# Square8.net
KiCad netlist of a schematic drawn in EAGLE
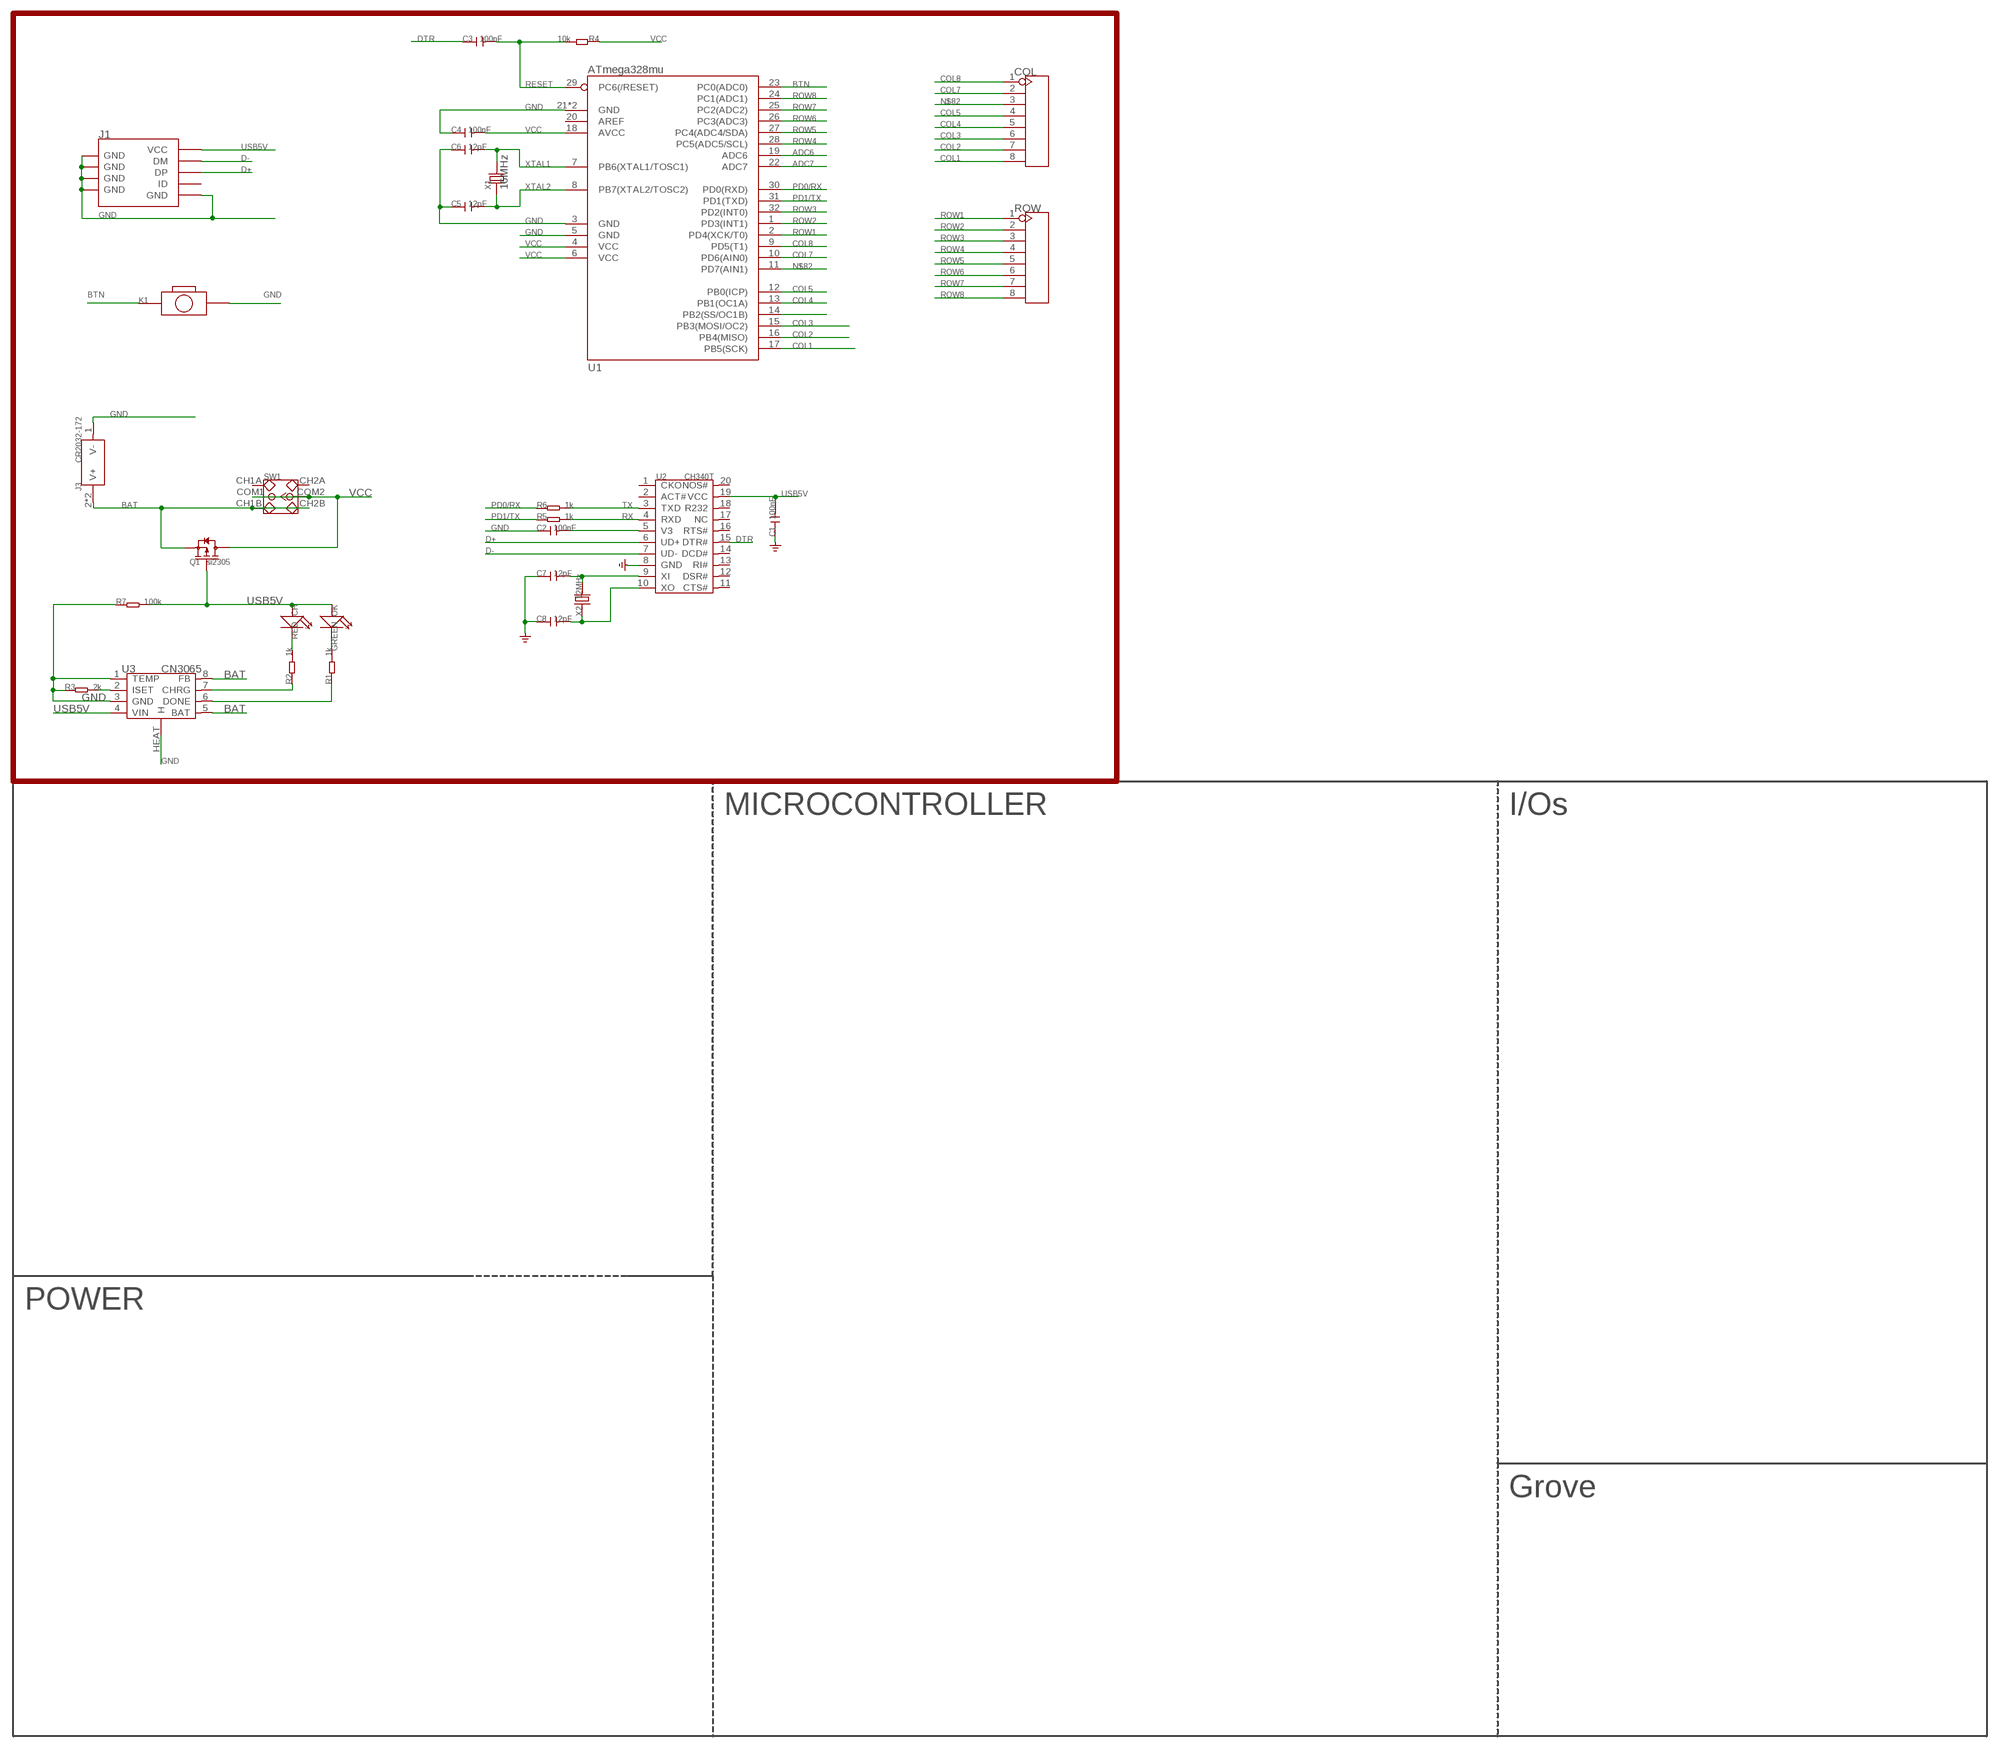
[diagram p0: schematic, sheet 1]

(export (version "E")
  (design (tool "Eeschema 10.0.6"))
  (components
    (comp (ref "C1")
      (value "100nF")
      (footprint "eagle-import:CERAMIC-2.54")
      (libsource (lib "eagle-import") (part "C'2.54'"))
    )
    (comp (ref "C2")
      (value "100nF")
      (footprint "eagle-import:CERAMIC-2.54")
      (libsource (lib "eagle-import") (part "C'2.54'"))
    )
    (comp (ref "C3")
      (value "100nF")
      (footprint "eagle-import:CERAMIC-2.54")
      (libsource (lib "eagle-import") (part "C'2.54'"))
    )
    (comp (ref "C4")
      (value "100nF")
      (footprint "eagle-import:CERAMIC-2.54")
      (libsource (lib "eagle-import") (part "C'2.54'"))
    )
    (comp (ref "C5")
      (value "12pF")
      (footprint "eagle-import:C0603")
      (libsource (lib "eagle-import") (part "C-0603"))
    )
    (comp (ref "C6")
      (value "12pF")
      (footprint "eagle-import:C0603")
      (libsource (lib "eagle-import") (part "C-0603"))
    )
    (comp (ref "C7")
      (value "12pF")
      (footprint "eagle-import:C0603")
      (libsource (lib "eagle-import") (part "C-0603"))
    )
    (comp (ref "C8")
      (value "12pF")
      (footprint "eagle-import:C0603")
      (libsource (lib "eagle-import") (part "C-0603"))
    )
    (comp (ref "CH")
      (value "RED")
      (footprint "eagle-import:LED-2P-2.54-3MM")
      (libsource (lib "eagle-import") (part "LED-3MM"))
    )
    (comp (ref "COL")
      (value "HEADER-8P-2.54")
      (footprint "eagle-import:8P-2.54")
      (libsource (lib "eagle-import") (part "HEADER-8P-2.54"))
    )
    (comp (ref "J1")
      (value "USB-MINIUSB-5P-MICRO")
      (footprint "eagle-import:MICRO-USB")
      (libsource (lib "eagle-import") (part "USB-MINIUSB-5P-MICRO"))
    )
    (comp (ref "J3")
      (value "CR2032-172")
      (footprint "eagle-import:2032-D20-CIRCLE")
      (libsource (lib "eagle-import") (part "HOLDER-BAT-CIRCLE"))
    )
    (comp (ref "K1")
      (value "BUTTON-2P'TS-1101F'")
      (footprint "eagle-import:2P-3.4X6.0X3.55H-90D")
      (libsource (lib "eagle-import") (part "BUTTON-2P'TS-1101F'"))
    )
    (comp (ref "OK")
      (value "GREEN")
      (footprint "eagle-import:LED-2P-2.54-3MM")
      (libsource (lib "eagle-import") (part "LED-3MM"))
    )
    (comp (ref "Q1")
      (value "si2305")
      (footprint "eagle-import:SOT23")
      (libsource (lib "eagle-import") (part "MOSFET-P'SI2323CDS/SI2305DS{lt}BR{gt}'"))
    )
    (comp (ref "R1")
      (value "1k")
      (footprint "eagle-import:R0204_7")
      (libsource (lib "eagle-import") (part "R-0204/7"))
    )
    (comp (ref "R2")
      (value "1k")
      (footprint "eagle-import:R0204_7")
      (libsource (lib "eagle-import") (part "R-0204/7"))
    )
    (comp (ref "R3")
      (value "2k")
      (footprint "eagle-import:R0204_7")
      (libsource (lib "eagle-import") (part "R-0204/7"))
    )
    (comp (ref "R4")
      (value "10k")
      (footprint "eagle-import:R0204_7")
      (libsource (lib "eagle-import") (part "R-0204/7"))
    )
    (comp (ref "R5")
      (value "1k")
      (footprint "eagle-import:R0204_7")
      (libsource (lib "eagle-import") (part "R-0204/7"))
    )
    (comp (ref "R6")
      (value "1k")
      (footprint "eagle-import:R0204_7")
      (libsource (lib "eagle-import") (part "R-0204/7"))
    )
    (comp (ref "R7")
      (value "100k")
      (footprint "eagle-import:R0603")
      (libsource (lib "eagle-import") (part "R-0603"))
    )
    (comp (ref "ROW")
      (value "HEADER-8P-2.54")
      (footprint "eagle-import:8P-2.54")
      (libsource (lib "eagle-import") (part "HEADER-8P-2.54"))
    )
    (comp (ref "SW1")
      (value "SWITCH-2CH-6P'90D'")
      (footprint "eagle-import:6P-2CH-2.5-9.1X3.5X3.2H-90D")
      (libsource (lib "eagle-import") (part "SWITCH-2CH-6P'90D'"))
    )
    (comp (ref "U1")
      (value "ATmega328mu")
      (footprint "eagle-import:MLF32X-W_HEAT")
      (libsource (lib "eagle-import") (part "ATMEGA8/168/328MLF"))
    )
    (comp (ref "U2")
      (value "CH340T")
      (footprint "eagle-import:SSOP20")
      (libsource (lib "eagle-import") (part "CH340T"))
    )
    (comp (ref "U3")
      (value "CN3065")
      (footprint "eagle-import:DFN8")
      (libsource (lib "eagle-import") (part "CN3065"))
    )
    (comp (ref "X1")
      (value "16MHz")
      (footprint "eagle-import:HC49S")
      (libsource (lib "eagle-import") (part "CRYSTAL'HC49S'"))
    )
    (comp (ref "X2")
      (value "12MHz")
      (footprint "eagle-import:HC49S")
      (libsource (lib "eagle-import") (part "CRYSTAL'HC49S'"))
    )
  )
  (nets
    (net (code "1") (name "/ADC6") (class "Default")
      (node (ref "U1") (pin "19") (pinfunction "ADC6_19") (pintype "bidirectional"))
    )
    (net (code "2") (name "/ADC7") (class "Default")
      (node (ref "U1") (pin "22") (pinfunction "ADC7_22") (pintype "bidirectional"))
    )
    (net (code "3") (name "/BAT") (class "Default")
      (node (ref "J3") (pin "2") (pinfunction "V+_2") (pintype "bidirectional"))
      (node (ref "J3") (pin "3") (pinfunction "V+_3") (pintype "bidirectional"))
      (node (ref "Q1") (pin "2") (pinfunction "S_2") (pintype "passive"))
      (node (ref "SW1") (pin "CH1B") (pinfunction "CH1B_CH1B") (pintype "bidirectional"))
      (node (ref "SW1") (pin "CH2B") (pinfunction "CH2B_CH2B") (pintype "bidirectional"))
      (node (ref "U3") (pin "5") (pinfunction "BAT_5") (pintype "bidirectional"))
      (node (ref "U3") (pin "8") (pinfunction "FB_8") (pintype "input"))
    )
    (net (code "4") (name "/BTN") (class "Default")
      (node (ref "K1") (pin "P$1") (pinfunction "1_P$1") (pintype "bidirectional"))
      (node (ref "U1") (pin "23") (pinfunction "PC0(ADC0)_23") (pintype "bidirectional"))
    )
    (net (code "5") (name "/COL1") (class "Default")
      (node (ref "COL") (pin "8") (pinfunction "8_8") (pintype "bidirectional"))
      (node (ref "U1") (pin "17") (pinfunction "PB5(SCK)_17") (pintype "bidirectional"))
    )
    (net (code "6") (name "/COL2") (class "Default")
      (node (ref "COL") (pin "7") (pinfunction "7_7") (pintype "bidirectional"))
      (node (ref "U1") (pin "16") (pinfunction "PB4(MISO)_16") (pintype "bidirectional"))
    )
    (net (code "7") (name "/COL3") (class "Default")
      (node (ref "COL") (pin "6") (pinfunction "6_6") (pintype "bidirectional"))
      (node (ref "U1") (pin "15") (pinfunction "PB3(MOSI/OC2)_15") (pintype "bidirectional"))
    )
    (net (code "8") (name "/COL4") (class "Default")
      (node (ref "COL") (pin "5") (pinfunction "5_5") (pintype "bidirectional"))
      (node (ref "U1") (pin "13") (pinfunction "PB1(OC1A)_13") (pintype "bidirectional"))
    )
    (net (code "9") (name "/COL5") (class "Default")
      (node (ref "COL") (pin "4") (pinfunction "4_4") (pintype "bidirectional"))
      (node (ref "U1") (pin "12") (pinfunction "PB0(ICP)_12") (pintype "bidirectional"))
    )
    (net (code "10") (name "/COL7") (class "Default")
      (node (ref "COL") (pin "2") (pinfunction "2_2") (pintype "bidirectional"))
      (node (ref "U1") (pin "10") (pinfunction "PD6(AIN0)_10") (pintype "bidirectional"))
    )
    (net (code "11") (name "/COL8") (class "Default")
      (node (ref "COL") (pin "1") (pinfunction "1_1") (pintype "bidirectional"))
      (node (ref "U1") (pin "9") (pinfunction "PD5(T1)_9") (pintype "bidirectional"))
    )
    (net (code "12") (name "/D+") (class "Default")
      (node (ref "J1") (pin "3") (pinfunction "DP_3") (pintype "bidirectional"))
      (node (ref "U2") (pin "6") (pinfunction "UD+_6") (pintype "bidirectional"))
    )
    (net (code "13") (name "/D-") (class "Default")
      (node (ref "J1") (pin "2") (pinfunction "DM_2") (pintype "bidirectional"))
      (node (ref "U2") (pin "7") (pinfunction "UD-_7") (pintype "bidirectional"))
    )
    (net (code "14") (name "/DTR") (class "Default")
      (node (ref "C3") (pin "1") (pinfunction "1_1") (pintype "passive"))
      (node (ref "U2") (pin "15") (pinfunction "DTR#_15") (pintype "output"))
    )
    (net (code "15") (name "/N$82") (class "Default")
      (node (ref "COL") (pin "3") (pinfunction "3_3") (pintype "bidirectional"))
      (node (ref "U1") (pin "11") (pinfunction "PD7(AIN1)_11") (pintype "bidirectional"))
    )
    (net (code "16") (name "/NOS#") (class "Default")
      (node (ref "U2") (pin "20") (pinfunction "NOS#_20") (pintype "power_in"))
    )
    (net (code "17") (name "/PD0{slash}RX") (class "Default")
      (node (ref "R6") (pin "1") (pinfunction "1_1") (pintype "passive"))
      (node (ref "U1") (pin "30") (pinfunction "PD0(RXD)_30") (pintype "bidirectional"))
    )
    (net (code "18") (name "/PD1{slash}TX") (class "Default")
      (node (ref "R5") (pin "1") (pinfunction "1_1") (pintype "passive"))
      (node (ref "U1") (pin "31") (pinfunction "PD1(TXD)_31") (pintype "bidirectional"))
    )
    (net (code "19") (name "/RESET") (class "Default")
      (node (ref "C3") (pin "2") (pinfunction "2_2") (pintype "passive"))
      (node (ref "R4") (pin "2") (pinfunction "2_2") (pintype "passive"))
      (node (ref "U1") (pin "29") (pinfunction "PC6(/RESET)_29") (pintype "bidirectional"))
    )
    (net (code "20") (name "/ROW1") (class "Default")
      (node (ref "ROW") (pin "1") (pinfunction "1_1") (pintype "bidirectional"))
      (node (ref "U1") (pin "2") (pinfunction "PD4(XCK/T0)_2") (pintype "bidirectional"))
    )
    (net (code "21") (name "/ROW2") (class "Default")
      (node (ref "ROW") (pin "2") (pinfunction "2_2") (pintype "bidirectional"))
      (node (ref "U1") (pin "1") (pinfunction "PD3(INT1)_1") (pintype "bidirectional"))
    )
    (net (code "22") (name "/ROW3") (class "Default")
      (node (ref "ROW") (pin "3") (pinfunction "3_3") (pintype "bidirectional"))
      (node (ref "U1") (pin "32") (pinfunction "PD2(INT0)_32") (pintype "bidirectional"))
    )
    (net (code "23") (name "/ROW4") (class "Default")
      (node (ref "ROW") (pin "4") (pinfunction "4_4") (pintype "bidirectional"))
      (node (ref "U1") (pin "28") (pinfunction "PC5(ADC5/SCL)_28") (pintype "bidirectional"))
    )
    (net (code "24") (name "/ROW5") (class "Default")
      (node (ref "ROW") (pin "5") (pinfunction "5_5") (pintype "bidirectional"))
      (node (ref "U1") (pin "27") (pinfunction "PC4(ADC4/SDA)_27") (pintype "bidirectional"))
    )
    (net (code "25") (name "/ROW6") (class "Default")
      (node (ref "ROW") (pin "6") (pinfunction "6_6") (pintype "bidirectional"))
      (node (ref "U1") (pin "26") (pinfunction "PC3(ADC3)_26") (pintype "bidirectional"))
    )
    (net (code "26") (name "/ROW7") (class "Default")
      (node (ref "ROW") (pin "7") (pinfunction "7_7") (pintype "bidirectional"))
      (node (ref "U1") (pin "25") (pinfunction "PC2(ADC2)_25") (pintype "bidirectional"))
    )
    (net (code "27") (name "/ROW8") (class "Default")
      (node (ref "ROW") (pin "8") (pinfunction "8_8") (pintype "bidirectional"))
      (node (ref "U1") (pin "24") (pinfunction "PC1(ADC1)_24") (pintype "bidirectional"))
    )
    (net (code "28") (name "/RX") (class "Default")
      (node (ref "R5") (pin "2") (pinfunction "2_2") (pintype "passive"))
      (node (ref "U2") (pin "4") (pinfunction "RXD_4") (pintype "input"))
    )
    (net (code "29") (name "/TX") (class "Default")
      (node (ref "R6") (pin "2") (pinfunction "2_2") (pintype "passive"))
      (node (ref "U2") (pin "3") (pinfunction "TXD_3") (pintype "output"))
    )
    (net (code "30") (name "/USB5V") (class "Default")
      (node (ref "C1") (pin "2") (pinfunction "2_2") (pintype "passive"))
      (node (ref "CH") (pin "A") (pinfunction "+_A") (pintype "passive"))
      (node (ref "J1") (pin "1") (pinfunction "VCC_1") (pintype "bidirectional"))
      (node (ref "OK") (pin "A") (pinfunction "+_A") (pintype "passive"))
      (node (ref "Q1") (pin "1") (pinfunction "G_1") (pintype "passive"))
      (node (ref "R7") (pin "2") (pinfunction "2_2") (pintype "passive"))
      (node (ref "U2") (pin "19") (pinfunction "VCC_19") (pintype "power_in"))
      (node (ref "U3") (pin "4") (pinfunction "VIN_4") (pintype "input"))
    )
    (net (code "31") (name "/VCC") (class "Default")
      (node (ref "C4") (pin "2") (pinfunction "2_2") (pintype "passive"))
      (node (ref "Q1") (pin "3") (pinfunction "D_3") (pintype "passive"))
      (node (ref "R4") (pin "1") (pinfunction "1_1") (pintype "passive"))
      (node (ref "SW1") (pin "COM1") (pinfunction "COM1_COM1") (pintype "bidirectional"))
      (node (ref "SW1") (pin "COM2") (pinfunction "COM2_COM2") (pintype "bidirectional"))
      (node (ref "U1") (pin "18") (pinfunction "AVCC_18") (pintype "bidirectional"))
      (node (ref "U1") (pin "4") (pinfunction "VCC_4") (pintype "bidirectional"))
      (node (ref "U1") (pin "6") (pinfunction "VCC_6") (pintype "bidirectional"))
    )
    (net (code "32") (name "/XTAL1") (class "Default")
      (node (ref "C6") (pin "2") (pinfunction "2_2") (pintype "passive"))
      (node (ref "U1") (pin "7") (pinfunction "PB6(XTAL1/TOSC1)_7") (pintype "bidirectional"))
      (node (ref "X1") (pin "2") (pinfunction "2_2") (pintype "passive"))
    )
    (net (code "33") (name "/XTAL2") (class "Default")
      (node (ref "C5") (pin "2") (pinfunction "2_2") (pintype "passive"))
      (node (ref "U1") (pin "8") (pinfunction "PB7(XTAL2/TOSC2)_8") (pintype "bidirectional"))
      (node (ref "X1") (pin "1") (pinfunction "1_1") (pintype "passive"))
    )
    (net (code "34") (name "GND_POWER") (class "Default")
      (node (ref "C1") (pin "1") (pinfunction "1_1") (pintype "passive"))
      (node (ref "C2") (pin "1") (pinfunction "1_1") (pintype "passive"))
      (node (ref "C4") (pin "1") (pinfunction "1_1") (pintype "passive"))
      (node (ref "C5") (pin "1") (pinfunction "1_1") (pintype "passive"))
      (node (ref "C6") (pin "1") (pinfunction "1_1") (pintype "passive"))
      (node (ref "C7") (pin "1") (pinfunction "1_1") (pintype "passive"))
      (node (ref "C8") (pin "1") (pinfunction "1_1") (pintype "passive"))
      (node (ref "J1") (pin "5") (pinfunction "GND_5") (pintype "bidirectional"))
      (node (ref "J1") (pin "S1") (pinfunction "GND_S1") (pintype "bidirectional"))
      (node (ref "J1") (pin "S2") (pinfunction "GND_S2") (pintype "bidirectional"))
      (node (ref "J1") (pin "S3") (pinfunction "GND_S3") (pintype "bidirectional"))
      (node (ref "J1") (pin "S4") (pinfunction "GND_S4") (pintype "bidirectional"))
      (node (ref "J1") (pin "S5") (pinfunction "GND_S5") (pintype "bidirectional"))
      (node (ref "J1") (pin "S6") (pinfunction "GND_S6") (pintype "bidirectional"))
      (node (ref "J3") (pin "1") (pinfunction "V-_1") (pintype "bidirectional"))
      (node (ref "K1") (pin "P$2") (pinfunction "2_P$2") (pintype "bidirectional"))
      (node (ref "R3") (pin "1") (pinfunction "1_1") (pintype "passive"))
      (node (ref "R7") (pin "1") (pinfunction "1_1") (pintype "passive"))
      (node (ref "U1") (pin "21") (pinfunction "GND_21") (pintype "bidirectional"))
      (node (ref "U1") (pin "3") (pinfunction "GND_3") (pintype "bidirectional"))
      (node (ref "U1") (pin "5") (pinfunction "GND_5") (pintype "bidirectional"))
      (node (ref "U1") (pin "HEAT") (pinfunction "GND_HEAT") (pintype "bidirectional"))
      (node (ref "U2") (pin "8") (pinfunction "GND_8") (pintype "power_in"))
      (node (ref "U3") (pin "1") (pinfunction "TEMP_1") (pintype "input"))
      (node (ref "U3") (pin "3") (pinfunction "GND_3") (pintype "power_in"))
      (node (ref "U3") (pin "HEAT") (pinfunction "H_HEAT") (pintype "bidirectional"))
    )
    (net (code "35") (name "Net-(CH--)") (class "Default")
      (node (ref "CH") (pin "K") (pinfunction "-_K") (pintype "passive"))
      (node (ref "R2") (pin "2") (pinfunction "2_2") (pintype "passive"))
    )
    (net (code "36") (name "Net-(OK--)") (class "Default")
      (node (ref "OK") (pin "K") (pinfunction "-_K") (pintype "passive"))
      (node (ref "R1") (pin "2") (pinfunction "2_2") (pintype "passive"))
    )
    (net (code "37") (name "Net-(U2-V3)") (class "Default")
      (node (ref "C2") (pin "2") (pinfunction "2_2") (pintype "passive"))
      (node (ref "U2") (pin "5") (pinfunction "V3_5") (pintype "power_in"))
    )
    (net (code "38") (name "Net-(U2-XI)") (class "Default")
      (node (ref "C7") (pin "2") (pinfunction "2_2") (pintype "passive"))
      (node (ref "U2") (pin "9") (pinfunction "XI_9") (pintype "input"))
      (node (ref "X2") (pin "2") (pinfunction "2_2") (pintype "passive"))
    )
    (net (code "39") (name "Net-(U2-XO)") (class "Default")
      (node (ref "C8") (pin "2") (pinfunction "2_2") (pintype "passive"))
      (node (ref "U2") (pin "10") (pinfunction "XO_10") (pintype "output"))
      (node (ref "X2") (pin "1") (pinfunction "1_1") (pintype "passive"))
    )
    (net (code "40") (name "Net-(U3-CHRG)") (class "Default")
      (node (ref "R2") (pin "1") (pinfunction "1_1") (pintype "passive"))
      (node (ref "U3") (pin "7") (pinfunction "CHRG_7") (pintype "bidirectional"))
    )
    (net (code "41") (name "Net-(U3-DONE)") (class "Default")
      (node (ref "R1") (pin "1") (pinfunction "1_1") (pintype "passive"))
      (node (ref "U3") (pin "6") (pinfunction "DONE_6") (pintype "bidirectional"))
    )
    (net (code "42") (name "Net-(U3-ISET)") (class "Default")
      (node (ref "R3") (pin "2") (pinfunction "2_2") (pintype "passive"))
      (node (ref "U3") (pin "2") (pinfunction "ISET_2") (pintype "bidirectional"))
    )
    (net (code "43") (name "unconnected-(J1-ID-Pad4)") (class "Default")
      (node (ref "J1") (pin "4") (pinfunction "ID_4") (pintype "bidirectional"))
    )
    (net (code "44") (name "unconnected-(SW1-PadCH1A)") (class "Default")
      (node (ref "SW1") (pin "CH1A") (pinfunction "CH1A_CH1A") (pintype "bidirectional"))
    )
    (net (code "45") (name "unconnected-(SW1-PadCH2A)") (class "Default")
      (node (ref "SW1") (pin "CH2A") (pinfunction "CH2A_CH2A") (pintype "bidirectional"))
    )
    (net (code "46") (name "unconnected-(U1-AREF-Pad20)") (class "Default")
      (node (ref "U1") (pin "20") (pinfunction "AREF_20") (pintype "bidirectional"))
    )
    (net (code "47") (name "unconnected-(U1-PB2(SS{slash}OC1B)-Pad14)") (class "Default")
      (node (ref "U1") (pin "14") (pinfunction "PB2(SS/OC1B)_14") (pintype "bidirectional"))
    )
    (net (code "48") (name "unconnected-(U2-ACT#-Pad2)") (class "Default")
      (node (ref "U2") (pin "2") (pinfunction "ACT#_2") (pintype "output"))
    )
    (net (code "49") (name "unconnected-(U2-CKO-Pad1)") (class "Default")
      (node (ref "U2") (pin "1") (pinfunction "CKO_1") (pintype "output"))
    )
    (net (code "50") (name "unconnected-(U2-CTS#-Pad11)") (class "Default")
      (node (ref "U2") (pin "11") (pinfunction "CTS#_11") (pintype "input"))
    )
    (net (code "51") (name "unconnected-(U2-DCD#-Pad14)") (class "Default")
      (node (ref "U2") (pin "14") (pinfunction "DCD#_14") (pintype "input"))
    )
    (net (code "52") (name "unconnected-(U2-DSR#-Pad12)") (class "Default")
      (node (ref "U2") (pin "12") (pinfunction "DSR#_12") (pintype "input"))
    )
    (net (code "53") (name "unconnected-(U2-NC-Pad17)") (class "Default")
      (node (ref "U2") (pin "17") (pinfunction "NC_17") (pintype "no_connect"))
    )
    (net (code "54") (name "unconnected-(U2-R232-Pad18)") (class "Default")
      (node (ref "U2") (pin "18") (pinfunction "R232_18") (pintype "input"))
    )
    (net (code "55") (name "unconnected-(U2-RI#-Pad13)") (class "Default")
      (node (ref "U2") (pin "13") (pinfunction "RI#_13") (pintype "input"))
    )
    (net (code "56") (name "unconnected-(U2-RTS#-Pad16)") (class "Default")
      (node (ref "U2") (pin "16") (pinfunction "RTS#_16") (pintype "output"))
    )
  )
)
